# 01_MAIN.net
KiCad netlist of a schematic drawn in Altium Designer
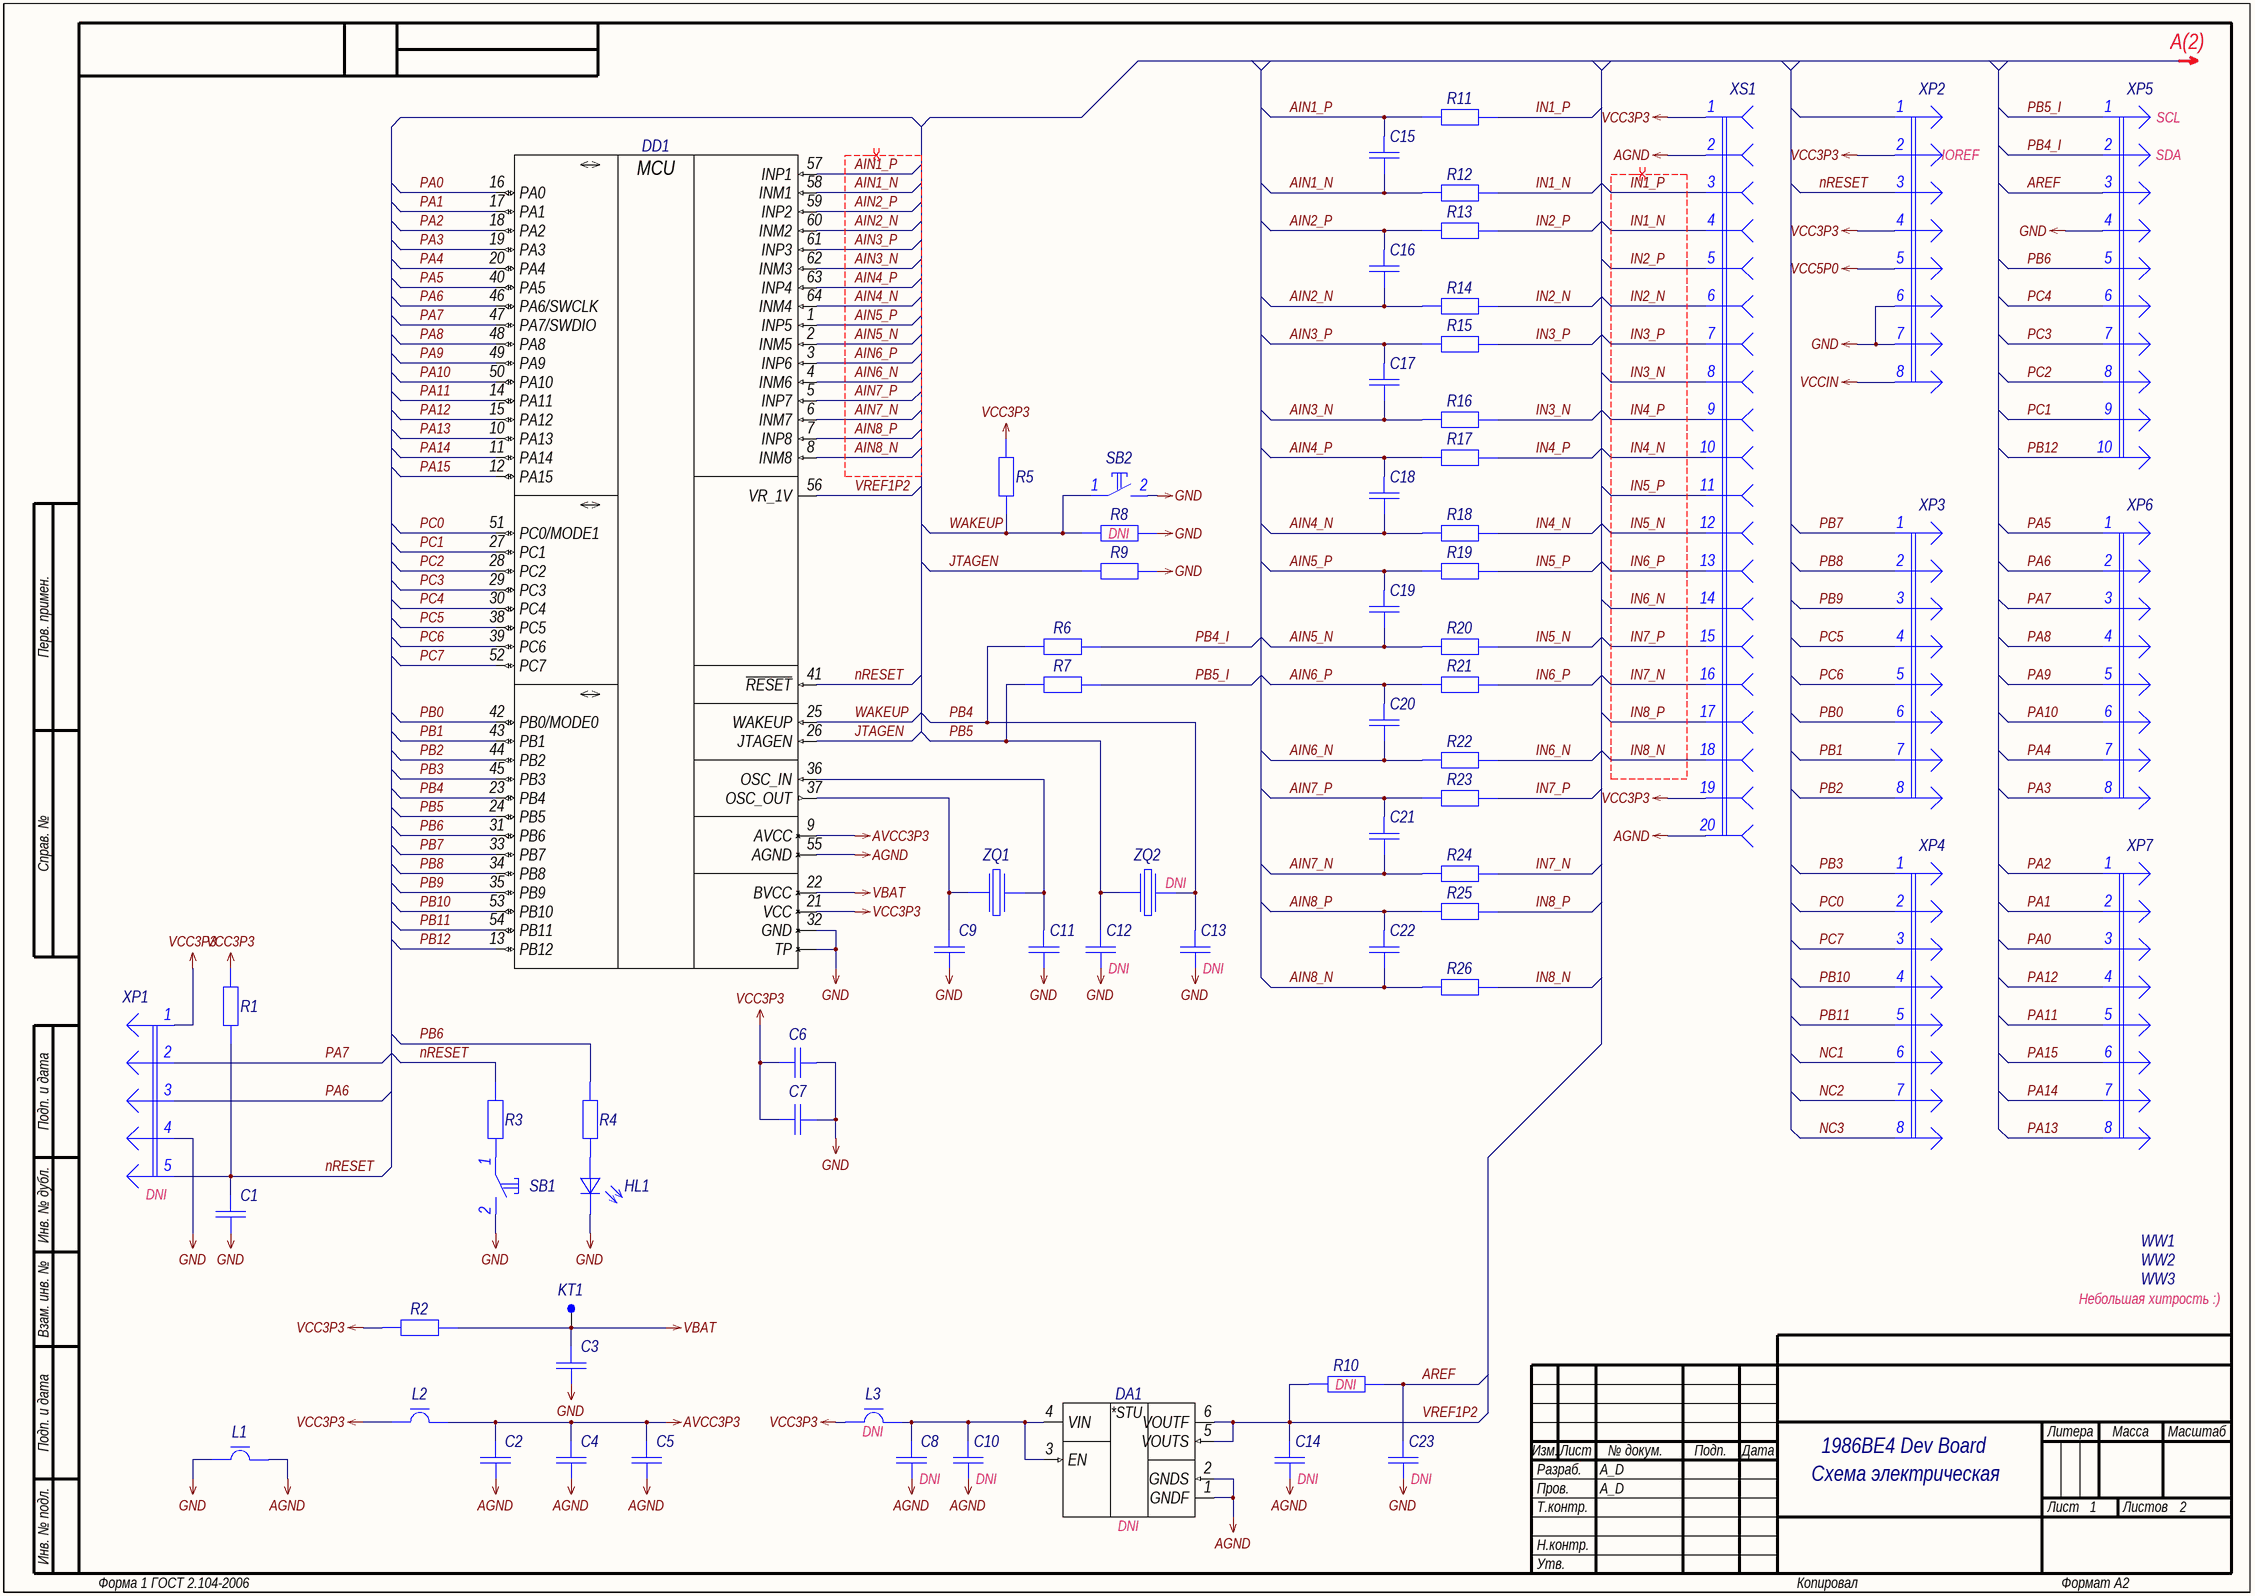
[diagram p0: 01_MAIN.SchDoc]

(export (version "E")
  (design (tool "Eeschema 10.0.6"))
  (components
    (comp (ref "C1")
      (value "Capacitor")
      (footprint "C0603_L")
      (fields
        (field (name "PART NUMBER") "GRM188R72A104KA35D")
        (field (name "VOLTAGE") "100V")
        (field (name "TOLERANCE") "±10%")
        (field (name "PUBLISHER") "Andrew Danich")
      )
      (libsource (lib "ADLib") (part "Capacitor"))
    )
    (comp (ref "C2")
      (value "Capacitor")
      (footprint "C0603_L")
      (fields
        (field (name "PART NUMBER") "GRM188R60J106ME47D")
        (field (name "VOLTAGE") "6.3V")
        (field (name "TOLERANCE") "±20%")
        (field (name "PUBLISHER") "Andrew Danich")
      )
      (libsource (lib "ADLib") (part "Capacitor"))
    )
    (comp (ref "C3")
      (value "Capacitor")
      (footprint "C0603_L")
      (fields
        (field (name "PART NUMBER") "GRM188R72A104KA35D")
        (field (name "VOLTAGE") "100V")
        (field (name "TOLERANCE") "±10%")
        (field (name "PUBLISHER") "Andrew Danich")
      )
      (libsource (lib "ADLib") (part "Capacitor"))
    )
    (comp (ref "C4")
      (value "Capacitor")
      (footprint "C0603_L")
      (fields
        (field (name "PART NUMBER") "GRM188R72A104KA35D")
        (field (name "VOLTAGE") "100V")
        (field (name "TOLERANCE") "±10%")
        (field (name "PUBLISHER") "Andrew Danich")
      )
      (libsource (lib "ADLib") (part "Capacitor"))
    )
    (comp (ref "C5")
      (value "Capacitor")
      (footprint "C0603_L")
      (fields
        (field (name "PART NUMBER") "GCJ188R72A103KA01D")
        (field (name "VOLTAGE") "100V")
        (field (name "TOLERANCE") "±10%")
        (field (name "PUBLISHER") "Andrew Danich")
      )
      (libsource (lib "ADLib") (part "Capacitor"))
    )
    (comp (ref "C6")
      (value "Capacitor")
      (footprint "C0603_L")
      (fields
        (field (name "PART NUMBER") "GRM188R72A104KA35D")
        (field (name "VOLTAGE") "100V")
        (field (name "TOLERANCE") "±10%")
        (field (name "PUBLISHER") "Andrew Danich")
      )
      (libsource (lib "ADLib") (part "Capacitor"))
    )
    (comp (ref "C7")
      (value "Capacitor")
      (footprint "C0603_L")
      (fields
        (field (name "PART NUMBER") "GCM188R71E105KA64D")
        (field (name "VOLTAGE") "25V")
        (field (name "TOLERANCE") "±10%")
        (field (name "PUBLISHER") "Andrew Danich")
      )
      (libsource (lib "ADLib") (part "Capacitor"))
    )
    (comp (ref "C8")
      (value "Capacitor")
      (footprint "C0603_L")
      (fields
        (field (name "PART NUMBER") "GCM188R71E105KA64D")
        (field (name "VOLTAGE") "25V")
        (field (name "TOLERANCE") "±10%")
        (field (name "PUBLISHER") "Andrew Danich")
      )
      (libsource (lib "ADLib") (part "Capacitor"))
    )
    (comp (ref "C9")
      (value "Capacitor")
      (footprint "C0603_L")
      (fields
        (field (name "PART NUMBER") "GCM1885C2A120JA16D")
        (field (name "VOLTAGE") "100V")
        (field (name "TOLERANCE") "±5%")
        (field (name "PUBLISHER") "Andrew Danich")
      )
      (libsource (lib "ADLib") (part "Capacitor"))
    )
    (comp (ref "C10")
      (value "Capacitor")
      (footprint "C0603_L")
      (fields
        (field (name "PART NUMBER") "GRM188R72A104KA35D")
        (field (name "VOLTAGE") "100V")
        (field (name "TOLERANCE") "±10%")
        (field (name "PUBLISHER") "Andrew Danich")
      )
      (libsource (lib "ADLib") (part "Capacitor"))
    )
    (comp (ref "C11")
      (value "Capacitor")
      (footprint "C0603_L")
      (fields
        (field (name "PART NUMBER") "GCM1885C2A120JA16D")
        (field (name "VOLTAGE") "100V")
        (field (name "TOLERANCE") "±5%")
        (field (name "PUBLISHER") "Andrew Danich")
      )
      (libsource (lib "ADLib") (part "Capacitor"))
    )
    (comp (ref "C12")
      (value "Capacitor")
      (footprint "C0603_L")
      (fields
        (field (name "PART NUMBER") "GCM1885C2A120JA16D")
        (field (name "VOLTAGE") "100V")
        (field (name "TOLERANCE") "±5%")
        (field (name "PUBLISHER") "Andrew Danich")
      )
      (libsource (lib "ADLib") (part "Capacitor"))
    )
    (comp (ref "C13")
      (value "Capacitor")
      (footprint "C0603_L")
      (fields
        (field (name "PART NUMBER") "GCM1885C2A120JA16D")
        (field (name "VOLTAGE") "100V")
        (field (name "TOLERANCE") "±5%")
        (field (name "PUBLISHER") "Andrew Danich")
      )
      (libsource (lib "ADLib") (part "Capacitor"))
    )
    (comp (ref "C14")
      (value "Capacitor")
      (footprint "C0603_L")
      (fields
        (field (name "PART NUMBER") "GRM188R72A104KA35D")
        (field (name "VOLTAGE") "100V")
        (field (name "TOLERANCE") "±10%")
        (field (name "PUBLISHER") "Andrew Danich")
      )
      (libsource (lib "ADLib") (part "Capacitor"))
    )
    (comp (ref "C15")
      (value "Capacitor")
      (footprint "C0603_L")
      (fields
        (field (name "PART NUMBER") "GCM1885C2A101JA16D")
        (field (name "VOLTAGE") "100V")
        (field (name "TOLERANCE") "±5%")
        (field (name "PUBLISHER") "Andrew Danich")
      )
      (libsource (lib "ADLib") (part "Capacitor"))
    )
    (comp (ref "C16")
      (value "Capacitor")
      (footprint "C0603_L")
      (fields
        (field (name "PART NUMBER") "GCM1885C2A101JA16D")
        (field (name "VOLTAGE") "100V")
        (field (name "TOLERANCE") "±5%")
        (field (name "PUBLISHER") "Andrew Danich")
      )
      (libsource (lib "ADLib") (part "Capacitor"))
    )
    (comp (ref "C17")
      (value "Capacitor")
      (footprint "C0603_L")
      (fields
        (field (name "PART NUMBER") "GCM1885C2A101JA16D")
        (field (name "VOLTAGE") "100V")
        (field (name "TOLERANCE") "±5%")
        (field (name "PUBLISHER") "Andrew Danich")
      )
      (libsource (lib "ADLib") (part "Capacitor"))
    )
    (comp (ref "C18")
      (value "Capacitor")
      (footprint "C0603_L")
      (fields
        (field (name "PART NUMBER") "GCM1885C2A101JA16D")
        (field (name "VOLTAGE") "100V")
        (field (name "TOLERANCE") "±5%")
        (field (name "PUBLISHER") "Andrew Danich")
      )
      (libsource (lib "ADLib") (part "Capacitor"))
    )
    (comp (ref "C19")
      (value "Capacitor")
      (footprint "C0603_L")
      (fields
        (field (name "PART NUMBER") "GCM1885C2A101JA16D")
        (field (name "VOLTAGE") "100V")
        (field (name "TOLERANCE") "±5%")
        (field (name "PUBLISHER") "Andrew Danich")
      )
      (libsource (lib "ADLib") (part "Capacitor"))
    )
    (comp (ref "C20")
      (value "Capacitor")
      (footprint "C0603_L")
      (fields
        (field (name "PART NUMBER") "GCM1885C2A101JA16D")
        (field (name "VOLTAGE") "100V")
        (field (name "TOLERANCE") "±5%")
        (field (name "PUBLISHER") "Andrew Danich")
      )
      (libsource (lib "ADLib") (part "Capacitor"))
    )
    (comp (ref "C21")
      (value "Capacitor")
      (footprint "C0603_L")
      (fields
        (field (name "PART NUMBER") "GCM1885C2A101JA16D")
        (field (name "VOLTAGE") "100V")
        (field (name "TOLERANCE") "±5%")
        (field (name "PUBLISHER") "Andrew Danich")
      )
      (libsource (lib "ADLib") (part "Capacitor"))
    )
    (comp (ref "C22")
      (value "Capacitor")
      (footprint "C0603_L")
      (fields
        (field (name "PART NUMBER") "GCM1885C2A101JA16D")
        (field (name "VOLTAGE") "100V")
        (field (name "TOLERANCE") "±5%")
        (field (name "PUBLISHER") "Andrew Danich")
      )
      (libsource (lib "ADLib") (part "Capacitor"))
    )
    (comp (ref "C23")
      (value "Capacitor")
      (footprint "C0603_L")
      (fields
        (field (name "PART NUMBER") "GRM188R72A104KA35D")
        (field (name "VOLTAGE") "100V")
        (field (name "TOLERANCE") "±10%")
        (field (name "PUBLISHER") "Andrew Danich")
      )
      (libsource (lib "ADLib") (part "Capacitor"))
    )
    (comp (ref "DA1")
      (value "ADR34xx-Series")
      (footprint "TSOT-23-6_095P290X160X100_N")
      (fields
        (field (name "PART NUMBER") "ADR3412ARJZ-R7")
        (field (name "MANUFACTURER") "Analog Devices")
        (field (name "PUBLISHER") "Andrew Danich")
      )
      (libsource (lib "ADLib") (part "ADR34xx-Series"))
    )
    (comp (ref "DD1")
      (value "1986ВЕ4У1-Series")
      (footprint "5153.64-1")
      (fields
        (field (name "PART NUMBER") "К1986ВЕ4У1К")
        (field (name "MANUFACTURER") "Миландр")
        (field (name "PUBLISHER") "Andrew Danich")
      )
      (libsource (lib "ADLib_RUS") (part "1986ВЕ4У1-Series"))
    )
    (comp (ref "HL1")
      (value "TEST")
      (footprint "LD0603_L")
      (fields (field (name "PART NUMBER") "BL-LS0603DNB") (field (name "PUBLISHER") "Andrew Danich"))
      (libsource (lib "ADLib") (part "Led-1"))
    )
    (comp (ref "KT1")
      (value "VBAT")
      (footprint "TP-SMT-C-0.8mm")
      (fields (field (name "PART NUMBER") "TestPoint-SMT") (field (name "PUBLISHER") "Andrew Danich"))
      (libsource (lib "ADLib") (part "TP-S-1"))
    )
    (comp (ref "L1")
      (value "FerriteBead")
      (footprint "L0805_L")
      (fields
        (field (name "PART NUMBER") "BLM21PG331SN1")
        (field (name "TOLERANCE") "±25%")
        (field (name "MANUFACTURER") "Murata")
        (field (name "PUBLISHER") "Andrew Danich")
      )
      (libsource (lib "ADLib") (part "FerriteBead"))
    )
    (comp (ref "L2")
      (value "FerriteBead")
      (footprint "L0603_L")
      (fields
        (field (name "PART NUMBER") "BLM18PG331SN1")
        (field (name "TOLERANCE") "±25%")
        (field (name "MANUFACTURER") "Murata")
        (field (name "PUBLISHER") "Andrew Danich")
      )
      (libsource (lib "ADLib") (part "FerriteBead"))
    )
    (comp (ref "L3")
      (value "FerriteBead")
      (footprint "L0603_L")
      (fields
        (field (name "PART NUMBER") "BLM18PG331SN1")
        (field (name "TOLERANCE") "±25%")
        (field (name "MANUFACTURER") "Murata")
        (field (name "PUBLISHER") "Andrew Danich")
      )
      (libsource (lib "ADLib") (part "FerriteBead"))
    )
    (comp (ref "R1")
      (value "Resistor")
      (footprint "R0603_L")
      (fields
        (field (name "PART NUMBER") "RC0603JR-0710KL")
        (field (name "TOLERANCE") "±5%")
        (field (name "MANUFACTURER") "Yageo")
        (field (name "PUBLISHER") "Andrew Danich")
      )
      (libsource (lib "ADLib") (part "Resistor"))
    )
    (comp (ref "R2")
      (value "Resistor")
      (footprint "R0603_L")
      (fields
        (field (name "PART NUMBER") "RC0603JR-070R")
        (field (name "TOLERANCE") "±5%")
        (field (name "MANUFACTURER") "Yageo")
        (field (name "PUBLISHER") "Andrew Danich")
      )
      (libsource (lib "ADLib") (part "Resistor"))
    )
    (comp (ref "R3")
      (value "Resistor")
      (footprint "R0603_L")
      (fields
        (field (name "PART NUMBER") "RC0603JR-07100R")
        (field (name "TOLERANCE") "±5%")
        (field (name "MANUFACTURER") "Yageo")
        (field (name "PUBLISHER") "Andrew Danich")
      )
      (libsource (lib "ADLib") (part "Resistor"))
    )
    (comp (ref "R4")
      (value "Resistor")
      (footprint "R0603_L")
      (fields
        (field (name "PART NUMBER") "RC0603JR-07330RL")
        (field (name "TOLERANCE") "±5%")
        (field (name "MANUFACTURER") "Yageo")
        (field (name "PUBLISHER") "Andrew Danich")
      )
      (libsource (lib "ADLib") (part "Resistor"))
    )
    (comp (ref "R5")
      (value "Resistor")
      (footprint "R0603_L")
      (fields
        (field (name "PART NUMBER") "RC0603JR-0710KL")
        (field (name "TOLERANCE") "±5%")
        (field (name "MANUFACTURER") "Yageo")
        (field (name "PUBLISHER") "Andrew Danich")
      )
      (libsource (lib "ADLib") (part "Resistor"))
    )
    (comp (ref "R6")
      (value "Resistor")
      (footprint "R0603_L")
      (fields
        (field (name "PART NUMBER") "RC0603JR-070R")
        (field (name "TOLERANCE") "±5%")
        (field (name "MANUFACTURER") "Yageo")
        (field (name "PUBLISHER") "Andrew Danich")
      )
      (libsource (lib "ADLib") (part "Resistor"))
    )
    (comp (ref "R7")
      (value "Resistor")
      (footprint "R0603_L")
      (fields
        (field (name "PART NUMBER") "RC0603JR-070R")
        (field (name "TOLERANCE") "±5%")
        (field (name "MANUFACTURER") "Yageo")
        (field (name "PUBLISHER") "Andrew Danich")
      )
      (libsource (lib "ADLib") (part "Resistor"))
    )
    (comp (ref "R8")
      (value "Resistor")
      (footprint "R0603_L")
      (fields
        (field (name "PART NUMBER") "RC0603JR-070R")
        (field (name "TOLERANCE") "±5%")
        (field (name "MANUFACTURER") "Yageo")
        (field (name "PUBLISHER") "Andrew Danich")
      )
      (libsource (lib "ADLib") (part "Resistor"))
    )
    (comp (ref "R9")
      (value "Resistor")
      (footprint "R0603_L")
      (fields
        (field (name "PART NUMBER") "RC0603JR-070R")
        (field (name "TOLERANCE") "±5%")
        (field (name "MANUFACTURER") "Yageo")
        (field (name "PUBLISHER") "Andrew Danich")
      )
      (libsource (lib "ADLib") (part "Resistor"))
    )
    (comp (ref "R10")
      (value "Resistor")
      (footprint "R0603_L")
      (fields
        (field (name "PART NUMBER") "RC0603JR-070R")
        (field (name "TOLERANCE") "±5%")
        (field (name "MANUFACTURER") "Yageo")
        (field (name "PUBLISHER") "Andrew Danich")
      )
      (libsource (lib "ADLib") (part "Resistor"))
    )
    (comp (ref "R11")
      (value "Resistor")
      (footprint "R0603_L")
      (fields
        (field (name "PART NUMBER") "RC0603FR-0749R9L")
        (field (name "TOLERANCE") "±1%")
        (field (name "MANUFACTURER") "Yageo")
        (field (name "PUBLISHER") "Andrew Danich")
      )
      (libsource (lib "ADLib") (part "Resistor"))
    )
    (comp (ref "R12")
      (value "Resistor")
      (footprint "R0603_L")
      (fields
        (field (name "PART NUMBER") "RC0603FR-0749R9L")
        (field (name "TOLERANCE") "±1%")
        (field (name "MANUFACTURER") "Yageo")
        (field (name "PUBLISHER") "Andrew Danich")
      )
      (libsource (lib "ADLib") (part "Resistor"))
    )
    (comp (ref "R13")
      (value "Resistor")
      (footprint "R0603_L")
      (fields
        (field (name "PART NUMBER") "RC0603FR-0749R9L")
        (field (name "TOLERANCE") "±1%")
        (field (name "MANUFACTURER") "Yageo")
        (field (name "PUBLISHER") "Andrew Danich")
      )
      (libsource (lib "ADLib") (part "Resistor"))
    )
    (comp (ref "R14")
      (value "Resistor")
      (footprint "R0603_L")
      (fields
        (field (name "PART NUMBER") "RC0603FR-0749R9L")
        (field (name "TOLERANCE") "±1%")
        (field (name "MANUFACTURER") "Yageo")
        (field (name "PUBLISHER") "Andrew Danich")
      )
      (libsource (lib "ADLib") (part "Resistor"))
    )
    (comp (ref "R15")
      (value "Resistor")
      (footprint "R0603_L")
      (fields
        (field (name "PART NUMBER") "RC0603FR-0749R9L")
        (field (name "TOLERANCE") "±1%")
        (field (name "MANUFACTURER") "Yageo")
        (field (name "PUBLISHER") "Andrew Danich")
      )
      (libsource (lib "ADLib") (part "Resistor"))
    )
    (comp (ref "R16")
      (value "Resistor")
      (footprint "R0603_L")
      (fields
        (field (name "PART NUMBER") "RC0603FR-0749R9L")
        (field (name "TOLERANCE") "±1%")
        (field (name "MANUFACTURER") "Yageo")
        (field (name "PUBLISHER") "Andrew Danich")
      )
      (libsource (lib "ADLib") (part "Resistor"))
    )
    (comp (ref "R17")
      (value "Resistor")
      (footprint "R0603_L")
      (fields
        (field (name "PART NUMBER") "RC0603FR-0749R9L")
        (field (name "TOLERANCE") "±1%")
        (field (name "MANUFACTURER") "Yageo")
        (field (name "PUBLISHER") "Andrew Danich")
      )
      (libsource (lib "ADLib") (part "Resistor"))
    )
    (comp (ref "R18")
      (value "Resistor")
      (footprint "R0603_L")
      (fields
        (field (name "PART NUMBER") "RC0603FR-0749R9L")
        (field (name "TOLERANCE") "±1%")
        (field (name "MANUFACTURER") "Yageo")
        (field (name "PUBLISHER") "Andrew Danich")
      )
      (libsource (lib "ADLib") (part "Resistor"))
    )
    (comp (ref "R19")
      (value "Resistor")
      (footprint "R0603_L")
      (fields
        (field (name "PART NUMBER") "RC0603FR-0749R9L")
        (field (name "TOLERANCE") "±1%")
        (field (name "MANUFACTURER") "Yageo")
        (field (name "PUBLISHER") "Andrew Danich")
      )
      (libsource (lib "ADLib") (part "Resistor"))
    )
    (comp (ref "R20")
      (value "Resistor")
      (footprint "R0603_L")
      (fields
        (field (name "PART NUMBER") "RC0603FR-0749R9L")
        (field (name "TOLERANCE") "±1%")
        (field (name "MANUFACTURER") "Yageo")
        (field (name "PUBLISHER") "Andrew Danich")
      )
      (libsource (lib "ADLib") (part "Resistor"))
    )
    (comp (ref "R21")
      (value "Resistor")
      (footprint "R0603_L")
      (fields
        (field (name "PART NUMBER") "RC0603FR-0749R9L")
        (field (name "TOLERANCE") "±1%")
        (field (name "MANUFACTURER") "Yageo")
        (field (name "PUBLISHER") "Andrew Danich")
      )
      (libsource (lib "ADLib") (part "Resistor"))
    )
    (comp (ref "R22")
      (value "Resistor")
      (footprint "R0603_L")
      (fields
        (field (name "PART NUMBER") "RC0603FR-0749R9L")
        (field (name "TOLERANCE") "±1%")
        (field (name "MANUFACTURER") "Yageo")
        (field (name "PUBLISHER") "Andrew Danich")
      )
      (libsource (lib "ADLib") (part "Resistor"))
    )
    (comp (ref "R23")
      (value "Resistor")
      (footprint "R0603_L")
      (fields
        (field (name "PART NUMBER") "RC0603FR-0749R9L")
        (field (name "TOLERANCE") "±1%")
        (field (name "MANUFACTURER") "Yageo")
        (field (name "PUBLISHER") "Andrew Danich")
      )
      (libsource (lib "ADLib") (part "Resistor"))
    )
    (comp (ref "R24")
      (value "Resistor")
      (footprint "R0603_L")
      (fields
        (field (name "PART NUMBER") "RC0603FR-0749R9L")
        (field (name "TOLERANCE") "±1%")
        (field (name "MANUFACTURER") "Yageo")
        (field (name "PUBLISHER") "Andrew Danich")
      )
      (libsource (lib "ADLib") (part "Resistor"))
    )
    (comp (ref "R25")
      (value "Resistor")
      (footprint "R0603_L")
      (fields
        (field (name "PART NUMBER") "RC0603FR-0749R9L")
        (field (name "TOLERANCE") "±1%")
        (field (name "MANUFACTURER") "Yageo")
        (field (name "PUBLISHER") "Andrew Danich")
      )
      (libsource (lib "ADLib") (part "Resistor"))
    )
    (comp (ref "R26")
      (value "Resistor")
      (footprint "R0603_L")
      (fields
        (field (name "PART NUMBER") "RC0603FR-0749R9L")
        (field (name "TOLERANCE") "±1%")
        (field (name "MANUFACTURER") "Yageo")
        (field (name "PUBLISHER") "Andrew Danich")
      )
      (libsource (lib "ADLib") (part "Resistor"))
    )
    (comp (ref "SB1")
      (value "СБРОС")
      (footprint "IT-1185AP")
      (fields (field (name "PART NUMBER") "IT-1185AP") (field (name "PUBLISHER") "Andrew Danich"))
      (libsource (lib "ADLib") (part "BT-01x-01p"))
    )
    (comp (ref "SB2")
      (value "WAKEUP")
      (footprint "IT-1185AP")
      (fields (field (name "PART NUMBER") "IT-1185AP") (field (name "PUBLISHER") "Andrew Danich"))
      (libsource (lib "ADLib") (part "BT-01x-01p"))
    )
    (comp (ref "WW1")
      (value "NoBody")
      (footprint "Mark-Fiducial_2.00mm")
      (fields (field (name "PART NUMBER") "MARK_FIDUCIAL") (field (name "PUBLISHER") "Andrew Danich"))
      (libsource (lib "ADLib") (part "NoBody"))
    )
    (comp (ref "WW2")
      (value "NoBody")
      (footprint "Mark-Fiducial_2.00mm")
      (fields (field (name "PART NUMBER") "MARK_FIDUCIAL") (field (name "PUBLISHER") "Andrew Danich"))
      (libsource (lib "ADLib") (part "NoBody"))
    )
    (comp (ref "WW3")
      (value "NoBody")
      (footprint "Mark-Fiducial_2.00mm")
      (fields (field (name "PART NUMBER") "MARK_FIDUCIAL") (field (name "PUBLISHER") "Andrew Danich"))
      (libsource (lib "ADLib") (part "NoBody"))
    )
    (comp (ref "XP1")
      (value "Prog")
      (footprint "PLS-5")
      (fields (field (name "PART NUMBER") "PLS-5") (field (name "PUBLISHER") "Andrew Danich"))
      (libsource (lib "ADLib") (part "Con-5-M"))
    )
    (comp (ref "XP2")
      (value "Text")
      (footprint "PLS-8")
      (fields (field (name "PART NUMBER") "PLS-8") (field (name "PUBLISHER") "Andrew Danich"))
      (libsource (lib "ADLib") (part "Con-8-M"))
    )
    (comp (ref "XP3")
      (value "Text")
      (footprint "PLS-8")
      (fields (field (name "PART NUMBER") "PLS-8") (field (name "PUBLISHER") "Andrew Danich"))
      (libsource (lib "ADLib") (part "Con-8-M"))
    )
    (comp (ref "XP4")
      (value "Text")
      (footprint "PLS-8")
      (fields (field (name "PART NUMBER") "PLS-8") (field (name "PUBLISHER") "Andrew Danich"))
      (libsource (lib "ADLib") (part "Con-8-M"))
    )
    (comp (ref "XP5")
      (value "Text")
      (footprint "PLS-10")
      (fields (field (name "PART NUMBER") "PLS-10") (field (name "PUBLISHER") "Andrew Danich"))
      (libsource (lib "ADLib") (part "Con-10-M"))
    )
    (comp (ref "XP6")
      (value "Text")
      (footprint "PLS-8")
      (fields (field (name "PART NUMBER") "PLS-8") (field (name "PUBLISHER") "Andrew Danich"))
      (libsource (lib "ADLib") (part "Con-8-M"))
    )
    (comp (ref "XP7")
      (value "Text")
      (footprint "PLS-8")
      (fields (field (name "PART NUMBER") "PLS-8") (field (name "PUBLISHER") "Andrew Danich"))
      (libsource (lib "ADLib") (part "Con-8-M"))
    )
    (comp (ref "XS1")
      (value "ADC")
      (footprint "PBD-20")
      (fields (field (name "PART NUMBER") "PBD-20") (field (name "PUBLISHER") "Andrew Danich"))
      (libsource (lib "ADLib") (part "Con-20-F"))
    )
    (comp (ref "ZQ1")
      (value "Crystal")
      (footprint "SMD 5x3.2mm")
      (fields (field (name "PART NUMBER") "AB-16.000MAGE-T") (field (name "PUBLISHER") "Andrew Danich"))
      (libsource (lib "ADLib") (part "Crystal"))
    )
    (comp (ref "ZQ2")
      (value "Crystal-1_4p")
      (footprint "DSO-N4")
      (fields
        (field (name "PART NUMBER") "MC306-32.768KHz")
        (field (name "MANUFACTURER") "Seiko Epson Corporation")
        (field (name "PUBLISHER") "Andrew Danich")
      )
      (libsource (lib "ADLib") (part "Crystal-1_4p"))
    )
  )
  (nets
    (net (code "1") (name "/AIN1_N") (class "Default")
      (node (ref "C15") (pin "1") (pinfunction "1_1") (pintype "passive"))
      (node (ref "DD1") (pin "58") (pinfunction "INM1_58") (pintype "input"))
      (node (ref "R12") (pin "1") (pinfunction "1_1") (pintype "passive"))
    )
    (net (code "2") (name "/AIN1_P") (class "Default")
      (node (ref "C15") (pin "2") (pinfunction "2_2") (pintype "passive"))
      (node (ref "DD1") (pin "57") (pinfunction "INP1_57") (pintype "input"))
      (node (ref "R11") (pin "1") (pinfunction "1_1") (pintype "passive"))
    )
    (net (code "3") (name "/AIN2_N") (class "Default")
      (node (ref "C16") (pin "1") (pinfunction "1_1") (pintype "passive"))
      (node (ref "DD1") (pin "60") (pinfunction "INM2_60") (pintype "input"))
      (node (ref "R14") (pin "1") (pinfunction "1_1") (pintype "passive"))
    )
    (net (code "4") (name "/AIN2_P") (class "Default")
      (node (ref "C16") (pin "2") (pinfunction "2_2") (pintype "passive"))
      (node (ref "DD1") (pin "59") (pinfunction "INP2_59") (pintype "input"))
      (node (ref "R13") (pin "1") (pinfunction "1_1") (pintype "passive"))
    )
    (net (code "5") (name "/AIN3_N") (class "Default")
      (node (ref "C17") (pin "1") (pinfunction "1_1") (pintype "passive"))
      (node (ref "DD1") (pin "62") (pinfunction "INM3_62") (pintype "input"))
      (node (ref "R16") (pin "1") (pinfunction "1_1") (pintype "passive"))
    )
    (net (code "6") (name "/AIN3_P") (class "Default")
      (node (ref "C17") (pin "2") (pinfunction "2_2") (pintype "passive"))
      (node (ref "DD1") (pin "61") (pinfunction "INP3_61") (pintype "input"))
      (node (ref "R15") (pin "1") (pinfunction "1_1") (pintype "passive"))
    )
    (net (code "7") (name "/AIN4_N") (class "Default")
      (node (ref "C18") (pin "1") (pinfunction "1_1") (pintype "passive"))
      (node (ref "DD1") (pin "64") (pinfunction "INM4_64") (pintype "input"))
      (node (ref "R18") (pin "1") (pinfunction "1_1") (pintype "passive"))
    )
    (net (code "8") (name "/AIN4_P") (class "Default")
      (node (ref "C18") (pin "2") (pinfunction "2_2") (pintype "passive"))
      (node (ref "DD1") (pin "63") (pinfunction "INP4_63") (pintype "input"))
      (node (ref "R17") (pin "1") (pinfunction "1_1") (pintype "passive"))
    )
    (net (code "9") (name "/AIN5_N") (class "Default")
      (node (ref "C19") (pin "1") (pinfunction "1_1") (pintype "passive"))
      (node (ref "DD1") (pin "2") (pinfunction "INM5_2") (pintype "input"))
      (node (ref "R20") (pin "1") (pinfunction "1_1") (pintype "passive"))
    )
    (net (code "10") (name "/AIN5_P") (class "Default")
      (node (ref "C19") (pin "2") (pinfunction "2_2") (pintype "passive"))
      (node (ref "DD1") (pin "1") (pinfunction "INP5_1") (pintype "input"))
      (node (ref "R19") (pin "1") (pinfunction "1_1") (pintype "passive"))
    )
    (net (code "11") (name "/AIN6_N") (class "Default")
      (node (ref "C20") (pin "1") (pinfunction "1_1") (pintype "passive"))
      (node (ref "DD1") (pin "4") (pinfunction "INM6_4") (pintype "input"))
      (node (ref "R22") (pin "1") (pinfunction "1_1") (pintype "passive"))
    )
    (net (code "12") (name "/AIN6_P") (class "Default")
      (node (ref "C20") (pin "2") (pinfunction "2_2") (pintype "passive"))
      (node (ref "DD1") (pin "3") (pinfunction "INP6_3") (pintype "input"))
      (node (ref "R21") (pin "1") (pinfunction "1_1") (pintype "passive"))
    )
    (net (code "13") (name "/AIN7_N") (class "Default")
      (node (ref "C21") (pin "1") (pinfunction "1_1") (pintype "passive"))
      (node (ref "DD1") (pin "6") (pinfunction "INM7_6") (pintype "input"))
      (node (ref "R24") (pin "1") (pinfunction "1_1") (pintype "passive"))
    )
    (net (code "14") (name "/AIN7_P") (class "Default")
      (node (ref "C21") (pin "2") (pinfunction "2_2") (pintype "passive"))
      (node (ref "DD1") (pin "5") (pinfunction "INP7_5") (pintype "input"))
      (node (ref "R23") (pin "1") (pinfunction "1_1") (pintype "passive"))
    )
    (net (code "15") (name "/AIN8_N") (class "Default")
      (node (ref "C22") (pin "1") (pinfunction "1_1") (pintype "passive"))
      (node (ref "DD1") (pin "8") (pinfunction "INM8_8") (pintype "input"))
      (node (ref "R26") (pin "1") (pinfunction "1_1") (pintype "passive"))
    )
    (net (code "16") (name "/AIN8_P") (class "Default")
      (node (ref "C22") (pin "2") (pinfunction "2_2") (pintype "passive"))
      (node (ref "DD1") (pin "7") (pinfunction "INP8_7") (pintype "input"))
      (node (ref "R25") (pin "1") (pinfunction "1_1") (pintype "passive"))
    )
    (net (code "17") (name "/AREF") (class "Default")
      (node (ref "C23") (pin "2") (pinfunction "2_2") (pintype "passive"))
      (node (ref "R10") (pin "2") (pinfunction "2_2") (pintype "passive"))
      (node (ref "XP5") (pin "3") (pintype "passive"))
    )
    (net (code "18") (name "/IN1_N") (class "Default")
      (node (ref "R12") (pin "2") (pinfunction "2_2") (pintype "passive"))
      (node (ref "XS1") (pin "4") (pintype "passive"))
    )
    (net (code "19") (name "/IN1_P") (class "Default")
      (node (ref "R11") (pin "2") (pinfunction "2_2") (pintype "passive"))
      (node (ref "XS1") (pin "3") (pintype "passive"))
    )
    (net (code "20") (name "/IN2_N") (class "Default")
      (node (ref "R14") (pin "2") (pinfunction "2_2") (pintype "passive"))
      (node (ref "XS1") (pin "6") (pintype "passive"))
    )
    (net (code "21") (name "/IN2_P") (class "Default")
      (node (ref "R13") (pin "2") (pinfunction "2_2") (pintype "passive"))
      (node (ref "XS1") (pin "5") (pintype "passive"))
    )
    (net (code "22") (name "/IN3_N") (class "Default")
      (node (ref "R16") (pin "2") (pinfunction "2_2") (pintype "passive"))
      (node (ref "XS1") (pin "8") (pintype "passive"))
    )
    (net (code "23") (name "/IN3_P") (class "Default")
      (node (ref "R15") (pin "2") (pinfunction "2_2") (pintype "passive"))
      (node (ref "XS1") (pin "7") (pintype "passive"))
    )
    (net (code "24") (name "/IN4_N") (class "Default")
      (node (ref "R18") (pin "2") (pinfunction "2_2") (pintype "passive"))
      (node (ref "XS1") (pin "10") (pintype "passive"))
    )
    (net (code "25") (name "/IN4_P") (class "Default")
      (node (ref "R17") (pin "2") (pinfunction "2_2") (pintype "passive"))
      (node (ref "XS1") (pin "9") (pintype "passive"))
    )
    (net (code "26") (name "/IN5_N") (class "Default")
      (node (ref "R20") (pin "2") (pinfunction "2_2") (pintype "passive"))
      (node (ref "XS1") (pin "12") (pintype "passive"))
    )
    (net (code "27") (name "/IN5_P") (class "Default")
      (node (ref "R19") (pin "2") (pinfunction "2_2") (pintype "passive"))
      (node (ref "XS1") (pin "11") (pintype "passive"))
    )
    (net (code "28") (name "/IN6_N") (class "Default")
      (node (ref "R22") (pin "2") (pinfunction "2_2") (pintype "passive"))
      (node (ref "XS1") (pin "14") (pintype "passive"))
    )
    (net (code "29") (name "/IN6_P") (class "Default")
      (node (ref "R21") (pin "2") (pinfunction "2_2") (pintype "passive"))
      (node (ref "XS1") (pin "13") (pintype "passive"))
    )
    (net (code "30") (name "/IN7_N") (class "Default")
      (node (ref "R24") (pin "2") (pinfunction "2_2") (pintype "passive"))
      (node (ref "XS1") (pin "16") (pintype "passive"))
    )
    (net (code "31") (name "/IN7_P") (class "Default")
      (node (ref "R23") (pin "2") (pinfunction "2_2") (pintype "passive"))
      (node (ref "XS1") (pin "15") (pintype "passive"))
    )
    (net (code "32") (name "/IN8_N") (class "Default")
      (node (ref "R26") (pin "2") (pinfunction "2_2") (pintype "passive"))
      (node (ref "XS1") (pin "18") (pintype "passive"))
    )
    (net (code "33") (name "/IN8_P") (class "Default")
      (node (ref "R25") (pin "2") (pinfunction "2_2") (pintype "passive"))
      (node (ref "XS1") (pin "17") (pintype "passive"))
    )
    (net (code "34") (name "/JTAGEN") (class "Default")
      (node (ref "DD1") (pin "26") (pinfunction "JTAGEN_26") (pintype "input"))
      (node (ref "R9") (pin "1") (pinfunction "1_1") (pintype "passive"))
    )
    (net (code "35") (name "/NC1") (class "Default") (node (ref "XP4") (pin "6") (pintype "passive")))
    (net (code "36") (name "/NC2") (class "Default") (node (ref "XP4") (pin "7") (pintype "passive")))
    (net (code "37") (name "/NC3") (class "Default") (node (ref "XP4") (pin "8") (pintype "passive")))
    (net (code "38") (name "/PA0") (class "Default")
      (node (ref "DD1") (pin "16") (pinfunction "PA0_16") (pintype "bidirectional"))
      (node (ref "XP7") (pin "3") (pintype "passive"))
    )
    (net (code "39") (name "/PA1") (class "Default")
      (node (ref "DD1") (pin "17") (pinfunction "PA1_17") (pintype "bidirectional"))
      (node (ref "XP7") (pin "2") (pintype "passive"))
    )
    (net (code "40") (name "/PA2") (class "Default")
      (node (ref "DD1") (pin "18") (pinfunction "PA2_18") (pintype "bidirectional"))
      (node (ref "XP7") (pin "1") (pintype "passive"))
    )
    (net (code "41") (name "/PA3") (class "Default")
      (node (ref "DD1") (pin "19") (pinfunction "PA3_19") (pintype "bidirectional"))
      (node (ref "XP6") (pin "8") (pintype "passive"))
    )
    (net (code "42") (name "/PA4") (class "Default")
      (node (ref "DD1") (pin "20") (pinfunction "PA4_20") (pintype "bidirectional"))
      (node (ref "XP6") (pin "7") (pintype "passive"))
    )
    (net (code "43") (name "/PA5") (class "Default")
      (node (ref "DD1") (pin "40") (pinfunction "PA5_40") (pintype "bidirectional"))
      (node (ref "XP6") (pin "1") (pintype "passive"))
    )
    (net (code "44") (name "/PA6") (class "Default")
      (node (ref "DD1") (pin "46") (pinfunction "PA6/SWCLK_46") (pintype "bidirectional"))
      (node (ref "XP1") (pin "3") (pintype "passive"))
      (node (ref "XP6") (pin "2") (pintype "passive"))
    )
    (net (code "45") (name "/PA7") (class "Default")
      (node (ref "DD1") (pin "47") (pinfunction "PA7/SWDIO_47") (pintype "bidirectional"))
      (node (ref "XP1") (pin "2") (pintype "passive"))
      (node (ref "XP6") (pin "3") (pintype "passive"))
    )
    (net (code "46") (name "/PA8") (class "Default")
      (node (ref "DD1") (pin "48") (pinfunction "PA8_48") (pintype "bidirectional"))
      (node (ref "XP6") (pin "4") (pintype "passive"))
    )
    (net (code "47") (name "/PA9") (class "Default")
      (node (ref "DD1") (pin "49") (pinfunction "PA9_49") (pintype "bidirectional"))
      (node (ref "XP6") (pin "5") (pintype "passive"))
    )
    (net (code "48") (name "/PA10") (class "Default")
      (node (ref "DD1") (pin "50") (pinfunction "PA10_50") (pintype "bidirectional"))
      (node (ref "XP6") (pin "6") (pintype "passive"))
    )
    (net (code "49") (name "/PA11") (class "Default")
      (node (ref "DD1") (pin "14") (pinfunction "PA11_14") (pintype "bidirectional"))
      (node (ref "XP7") (pin "5") (pintype "passive"))
    )
    (net (code "50") (name "/PA12") (class "Default")
      (node (ref "DD1") (pin "15") (pinfunction "PA12_15") (pintype "bidirectional"))
      (node (ref "XP7") (pin "4") (pintype "passive"))
    )
    (net (code "51") (name "/PA13") (class "Default")
      (node (ref "DD1") (pin "10") (pinfunction "PA13_10") (pintype "bidirectional"))
      (node (ref "XP7") (pin "8") (pintype "passive"))
    )
    (net (code "52") (name "/PA14") (class "Default")
      (node (ref "DD1") (pin "11") (pinfunction "PA14_11") (pintype "bidirectional"))
      (node (ref "XP7") (pin "7") (pintype "passive"))
    )
    (net (code "53") (name "/PA15") (class "Default")
      (node (ref "DD1") (pin "12") (pinfunction "PA15_12") (pintype "bidirectional"))
      (node (ref "XP7") (pin "6") (pintype "passive"))
    )
    (net (code "54") (name "/PB0") (class "Default")
      (node (ref "DD1") (pin "42") (pinfunction "PB0/MODE0_42") (pintype "bidirectional"))
      (node (ref "XP3") (pin "6") (pintype "passive"))
    )
    (net (code "55") (name "/PB1") (class "Default")
      (node (ref "DD1") (pin "43") (pinfunction "PB1_43") (pintype "bidirectional"))
      (node (ref "XP3") (pin "7") (pintype "passive"))
    )
    (net (code "56") (name "/PB2") (class "Default")
      (node (ref "DD1") (pin "44") (pinfunction "PB2_44") (pintype "bidirectional"))
      (node (ref "XP3") (pin "8") (pintype "passive"))
    )
    (net (code "57") (name "/PB3") (class "Default")
      (node (ref "DD1") (pin "45") (pinfunction "PB3_45") (pintype "bidirectional"))
      (node (ref "XP4") (pin "1") (pintype "passive"))
    )
    (net (code "58") (name "/PB4") (class "Default")
      (node (ref "C13") (pin "2") (pinfunction "2_2") (pintype "passive"))
      (node (ref "DD1") (pin "23") (pinfunction "PB4_23") (pintype "bidirectional"))
      (node (ref "R6") (pin "1") (pinfunction "1_1") (pintype "passive"))
      (node (ref "ZQ2") (pin "1") (pinfunction "1_1") (pintype "passive"))
    )
    (net (code "59") (name "/PB4_I") (class "Default")
      (node (ref "R6") (pin "2") (pinfunction "2_2") (pintype "passive"))
      (node (ref "XP5") (pin "2") (pintype "passive"))
    )
    (net (code "60") (name "/PB5") (class "Default")
      (node (ref "C12") (pin "2") (pinfunction "2_2") (pintype "passive"))
      (node (ref "DD1") (pin "24") (pinfunction "PB5_24") (pintype "bidirectional"))
      (node (ref "R7") (pin "1") (pinfunction "1_1") (pintype "passive"))
      (node (ref "ZQ2") (pin "4") (pinfunction "4_4") (pintype "passive"))
    )
    (net (code "61") (name "/PB5_I") (class "Default")
      (node (ref "R7") (pin "2") (pinfunction "2_2") (pintype "passive"))
      (node (ref "XP5") (pin "1") (pintype "passive"))
    )
    (net (code "62") (name "/PB6") (class "Default")
      (node (ref "DD1") (pin "31") (pinfunction "PB6_31") (pintype "bidirectional"))
      (node (ref "R4") (pin "2") (pinfunction "2_2") (pintype "passive"))
      (node (ref "XP5") (pin "5") (pintype "passive"))
    )
    (net (code "63") (name "/PB7") (class "Default")
      (node (ref "DD1") (pin "33") (pinfunction "PB7_33") (pintype "bidirectional"))
      (node (ref "XP3") (pin "1") (pintype "passive"))
    )
    (net (code "64") (name "/PB8") (class "Default")
      (node (ref "DD1") (pin "34") (pinfunction "PB8_34") (pintype "bidirectional"))
      (node (ref "XP3") (pin "2") (pintype "passive"))
    )
    (net (code "65") (name "/PB9") (class "Default")
      (node (ref "DD1") (pin "35") (pinfunction "PB9_35") (pintype "bidirectional"))
      (node (ref "XP3") (pin "3") (pintype "passive"))
    )
    (net (code "66") (name "/PB10") (class "Default")
      (node (ref "DD1") (pin "53") (pinfunction "PB10_53") (pintype "bidirectional"))
      (node (ref "XP4") (pin "4") (pintype "passive"))
    )
    (net (code "67") (name "/PB11") (class "Default")
      (node (ref "DD1") (pin "54") (pinfunction "PB11_54") (pintype "bidirectional"))
      (node (ref "XP4") (pin "5") (pintype "passive"))
    )
    (net (code "68") (name "/PB12") (class "Default")
      (node (ref "DD1") (pin "13") (pinfunction "PB12_13") (pintype "bidirectional"))
      (node (ref "XP5") (pin "10") (pintype "passive"))
    )
    (net (code "69") (name "/PC0") (class "Default")
      (node (ref "DD1") (pin "51") (pinfunction "PC0/MODE1_51") (pintype "bidirectional"))
      (node (ref "XP4") (pin "2") (pintype "passive"))
    )
    (net (code "70") (name "/PC1") (class "Default")
      (node (ref "DD1") (pin "27") (pinfunction "PC1_27") (pintype "bidirectional"))
      (node (ref "XP5") (pin "9") (pintype "passive"))
    )
    (net (code "71") (name "/PC2") (class "Default")
      (node (ref "DD1") (pin "28") (pinfunction "PC2_28") (pintype "bidirectional"))
      (node (ref "XP5") (pin "8") (pintype "passive"))
    )
    (net (code "72") (name "/PC3") (class "Default")
      (node (ref "DD1") (pin "29") (pinfunction "PC3_29") (pintype "bidirectional"))
      (node (ref "XP5") (pin "7") (pintype "passive"))
    )
    (net (code "73") (name "/PC4") (class "Default")
      (node (ref "DD1") (pin "30") (pinfunction "PC4_30") (pintype "bidirectional"))
      (node (ref "XP5") (pin "6") (pintype "passive"))
    )
    (net (code "74") (name "/PC5") (class "Default")
      (node (ref "DD1") (pin "38") (pinfunction "PC5_38") (pintype "bidirectional"))
      (node (ref "XP3") (pin "4") (pintype "passive"))
    )
    (net (code "75") (name "/PC6") (class "Default")
      (node (ref "DD1") (pin "39") (pinfunction "PC6_39") (pintype "bidirectional"))
      (node (ref "XP3") (pin "5") (pintype "passive"))
    )
    (net (code "76") (name "/PC7") (class "Default")
      (node (ref "DD1") (pin "52") (pinfunction "PC7_52") (pintype "bidirectional"))
      (node (ref "XP4") (pin "3") (pintype "passive"))
    )
    (net (code "77") (name "/VREF1P2") (class "Default")
      (node (ref "C14") (pin "2") (pinfunction "2_2") (pintype "passive"))
      (node (ref "DA1") (pin "5") (pinfunction "VOUTS_5") (pintype "input"))
      (node (ref "DA1") (pin "6") (pinfunction "VOUTF_6") (pintype "power_in"))
      (node (ref "DD1") (pin "56") (pinfunction "VR_1V_56") (pintype "power_in"))
      (node (ref "R10") (pin "1") (pinfunction "1_1") (pintype "passive"))
    )
    (net (code "78") (name "/WAKEUP") (class "Default")
      (node (ref "DD1") (pin "25") (pinfunction "WAKEUP_25") (pintype "input"))
      (node (ref "R5") (pin "1") (pinfunction "1_1") (pintype "passive"))
      (node (ref "R8") (pin "1") (pinfunction "1_1") (pintype "passive"))
      (node (ref "SB2") (pin "1") (pintype "passive"))
    )
    (net (code "79") (name "/nRESET") (class "Default")
      (node (ref "C1") (pin "2") (pinfunction "2_2") (pintype "passive"))
      (node (ref "DD1") (pin "41") (pinfunction "~{RESET}_41") (pintype "input"))
      (node (ref "R1") (pin "1") (pinfunction "1_1") (pintype "passive"))
      (node (ref "R3") (pin "2") (pinfunction "2_2") (pintype "passive"))
      (node (ref "XP1") (pin "5") (pintype "passive"))
      (node (ref "XP2") (pin "3") (pintype "passive"))
    )
    (net (code "80") (name "AGND") (class "Default")
      (node (ref "C10") (pin "1") (pinfunction "1_1") (pintype "passive"))
      (node (ref "C14") (pin "1") (pinfunction "1_1") (pintype "passive"))
      (node (ref "C2") (pin "1") (pinfunction "1_1") (pintype "passive"))
      (node (ref "C4") (pin "1") (pinfunction "1_1") (pintype "passive"))
      (node (ref "C5") (pin "1") (pinfunction "1_1") (pintype "passive"))
      (node (ref "C8") (pin "1") (pinfunction "1_1") (pintype "passive"))
      (node (ref "DA1") (pin "1") (pinfunction "GNDF_1") (pintype "power_in"))
      (node (ref "DA1") (pin "2") (pinfunction "GNDS_2") (pintype "input"))
      (node (ref "DD1") (pin "55") (pinfunction "AGND_55") (pintype "power_in"))
      (node (ref "L1") (pin "2") (pinfunction "2_2") (pintype "passive"))
      (node (ref "XS1") (pin "2") (pintype "passive"))
      (node (ref "XS1") (pin "20") (pintype "passive"))
    )
    (net (code "81") (name "AVCC3P3") (class "Default")
      (node (ref "C2") (pin "2") (pinfunction "2_2") (pintype "passive"))
      (node (ref "C4") (pin "2") (pinfunction "2_2") (pintype "passive"))
      (node (ref "C5") (pin "2") (pinfunction "2_2") (pintype "passive"))
      (node (ref "DD1") (pin "9") (pinfunction "AVCC_9") (pintype "power_in"))
      (node (ref "L2") (pin "2") (pinfunction "2_2") (pintype "passive"))
    )
    (net (code "82") (name "GND") (class "Default")
      (node (ref "C1") (pin "1") (pinfunction "1_1") (pintype "passive"))
      (node (ref "C11") (pin "1") (pinfunction "1_1") (pintype "passive"))
      (node (ref "C12") (pin "1") (pinfunction "1_1") (pintype "passive"))
      (node (ref "C13") (pin "1") (pinfunction "1_1") (pintype "passive"))
      (node (ref "C23") (pin "1") (pinfunction "1_1") (pintype "passive"))
      (node (ref "C3") (pin "1") (pinfunction "1_1") (pintype "passive"))
      (node (ref "C6") (pin "1") (pinfunction "1_1") (pintype "passive"))
      (node (ref "C7") (pin "1") (pinfunction "1_1") (pintype "passive"))
      (node (ref "C9") (pin "1") (pinfunction "1_1") (pintype "passive"))
      (node (ref "DD1") (pin "32") (pinfunction "GND_32") (pintype "power_in"))
      (node (ref "DD1") (pin "TP") (pinfunction "TP_TP") (pintype "power_in"))
      (node (ref "HL1") (pin "2") (pinfunction "К_2") (pintype "passive"))
      (node (ref "L1") (pin "1") (pinfunction "1_1") (pintype "passive"))
      (node (ref "R8") (pin "2") (pinfunction "2_2") (pintype "passive"))
      (node (ref "R9") (pin "2") (pinfunction "2_2") (pintype "passive"))
      (node (ref "SB1") (pin "2") (pintype "passive"))
      (node (ref "SB2") (pin "2") (pintype "passive"))
      (node (ref "XP1") (pin "4") (pintype "passive"))
      (node (ref "XP2") (pin "6") (pintype "passive"))
      (node (ref "XP2") (pin "7") (pintype "passive"))
      (node (ref "XP5") (pin "4") (pintype "passive"))
    )
    (net (code "83") (name "Net-(DA1-EN)") (class "Default")
      (node (ref "C10") (pin "2") (pinfunction "2_2") (pintype "passive"))
      (node (ref "C8") (pin "2") (pinfunction "2_2") (pintype "passive"))
      (node (ref "DA1") (pin "3") (pinfunction "EN_3") (pintype "input"))
      (node (ref "DA1") (pin "4") (pinfunction "VIN_4") (pintype "power_in"))
      (node (ref "L3") (pin "2") (pinfunction "2_2") (pintype "passive"))
    )
    (net (code "84") (name "Net-(DD1-OSC_IN)") (class "Default")
      (node (ref "C11") (pin "2") (pinfunction "2_2") (pintype "passive"))
      (node (ref "DD1") (pin "36") (pinfunction "OSC_IN_36") (pintype "input"))
      (node (ref "ZQ1") (pin "3") (pinfunction "3_3") (pintype "passive"))
    )
    (net (code "85") (name "Net-(DD1-OSC_OUT)") (class "Default")
      (node (ref "C9") (pin "2") (pinfunction "2_2") (pintype "passive"))
      (node (ref "DD1") (pin "37") (pinfunction "OSC_OUT_37") (pintype "output"))
      (node (ref "ZQ1") (pin "1") (pinfunction "1_1") (pintype "passive"))
    )
    (net (code "86") (name "Net-(HL1-А)") (class "Default")
      (node (ref "HL1") (pin "1") (pinfunction "А_1") (pintype "passive"))
      (node (ref "R4") (pin "1") (pinfunction "1_1") (pintype "passive"))
    )
    (net (code "87") (name "Net-(R3-Pad1)") (class "Default")
      (node (ref "R3") (pin "1") (pinfunction "1_1") (pintype "passive"))
      (node (ref "SB1") (pin "1") (pintype "passive"))
    )
    (net (code "88") (name "VBAT") (class "Default")
      (node (ref "C3") (pin "2") (pinfunction "2_2") (pintype "passive"))
      (node (ref "DD1") (pin "22") (pinfunction "BVCC_22") (pintype "power_in"))
      (node (ref "KT1") (pin "1") (pinfunction "1_1") (pintype "passive"))
      (node (ref "R2") (pin "2") (pinfunction "2_2") (pintype "passive"))
    )
    (net (code "89") (name "VCC3P3") (class "Default")
      (node (ref "C6") (pin "2") (pinfunction "2_2") (pintype "passive"))
      (node (ref "C7") (pin "2") (pinfunction "2_2") (pintype "passive"))
      (node (ref "DD1") (pin "21") (pinfunction "VCC_21") (pintype "power_in"))
      (node (ref "L2") (pin "1") (pinfunction "1_1") (pintype "passive"))
      (node (ref "L3") (pin "1") (pinfunction "1_1") (pintype "passive"))
      (node (ref "R1") (pin "2") (pinfunction "2_2") (pintype "passive"))
      (node (ref "R2") (pin "1") (pinfunction "1_1") (pintype "passive"))
      (node (ref "R5") (pin "2") (pinfunction "2_2") (pintype "passive"))
      (node (ref "XP1") (pin "1") (pintype "passive"))
      (node (ref "XP2") (pin "2") (pintype "passive"))
      (node (ref "XP2") (pin "4") (pintype "passive"))
      (node (ref "XS1") (pin "1") (pintype "passive"))
      (node (ref "XS1") (pin "19") (pintype "passive"))
    )
    (net (code "90") (name "VCC5P0") (class "Default") (node (ref "XP2") (pin "5") (pintype "passive")))
    (net (code "91") (name "VCCIN") (class "Default") (node (ref "XP2") (pin "8") (pintype "passive")))
    (net (code "92") (name "unconnected-(XP2-Pad1)") (class "Default")
      (node (ref "XP2") (pin "1") (pintype "passive"))
    )
  )
)
